# MemoryControl.net
KiCad netlist of a schematic drawn in Altium Designer
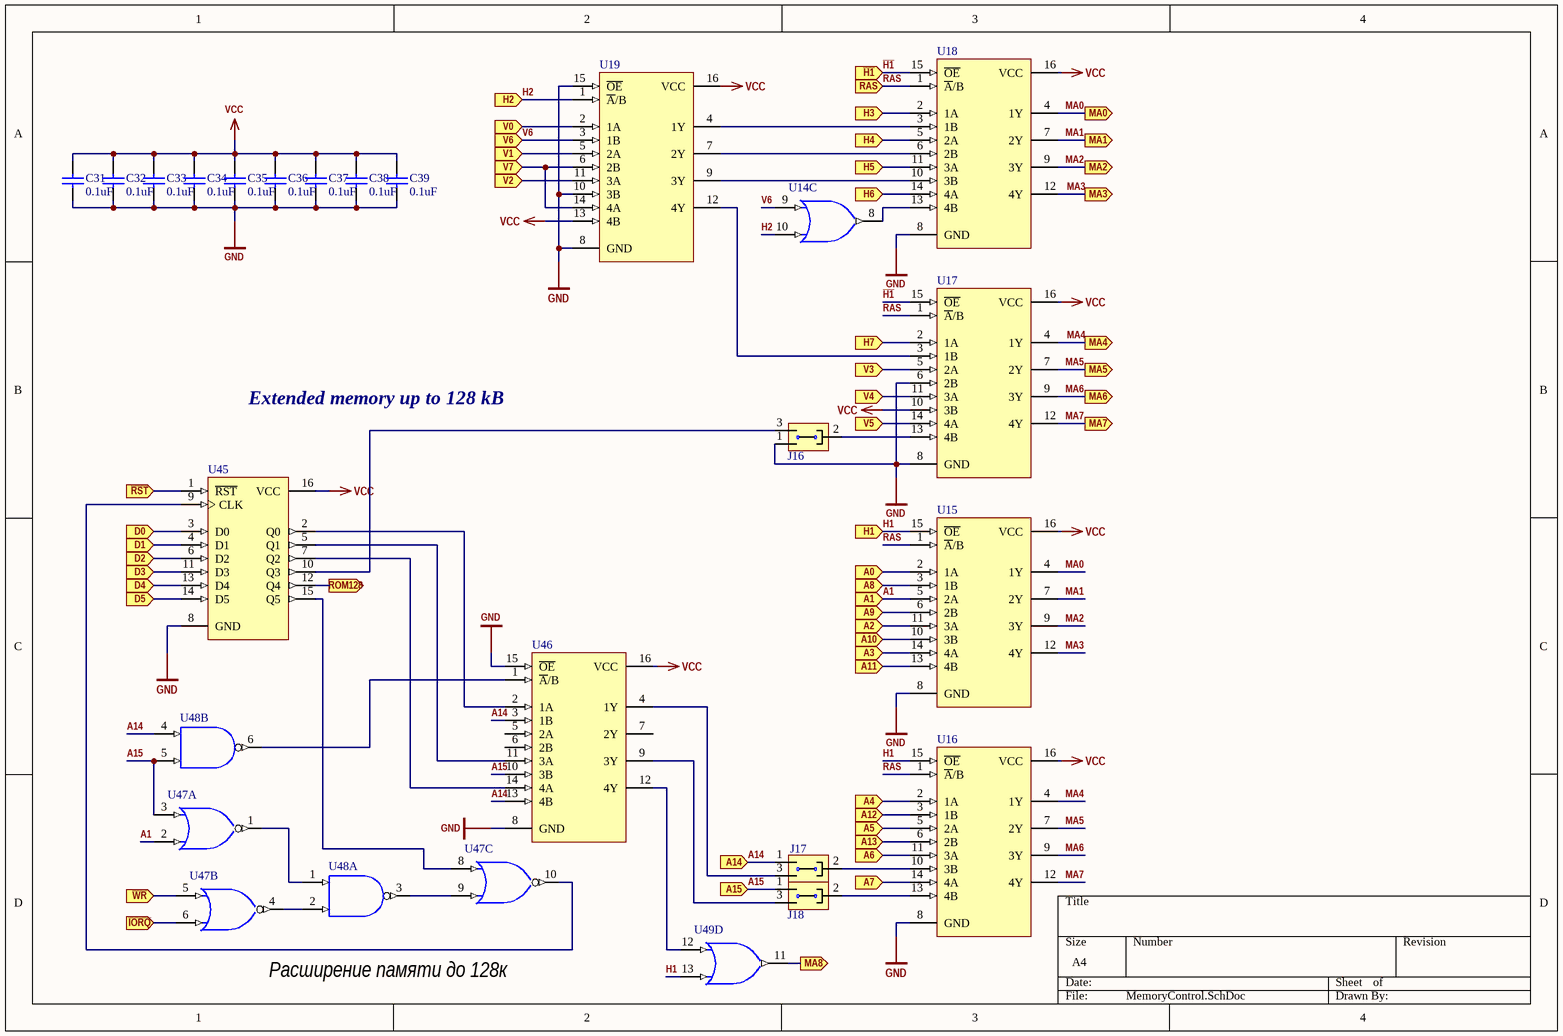
[diagram p0: MemoryControl.SchDoc]

(export (version "E")
  (design (tool "Eeschema 10.0.6"))
  (components
    (comp (ref "C31")
      (value "0.1uF")
      (footprint "RAD-0.3")
      (description "Capacitor")
      (fields (field (name "Comment") "Cap") (field (name "PUBLISHER") "Altium Limited"))
      (libsource (lib "Lenin") (part "Cap"))
    )
    (comp (ref "C32")
      (value "0.1uF")
      (footprint "RAD-0.3")
      (description "Capacitor")
      (fields (field (name "Comment") "Cap") (field (name "PUBLISHER") "Altium Limited"))
      (libsource (lib "Lenin") (part "Cap"))
    )
    (comp (ref "C33")
      (value "0.1uF")
      (footprint "RAD-0.3")
      (description "Capacitor")
      (fields (field (name "Comment") "Cap") (field (name "PUBLISHER") "Altium Limited"))
      (libsource (lib "Lenin") (part "Cap"))
    )
    (comp (ref "C34")
      (value "0.1uF")
      (footprint "RAD-0.3")
      (description "Capacitor")
      (fields (field (name "Comment") "Cap") (field (name "PUBLISHER") "Altium Limited"))
      (libsource (lib "Lenin") (part "Cap"))
    )
    (comp (ref "C35")
      (value "0.1uF")
      (footprint "RAD-0.3")
      (description "Capacitor")
      (fields (field (name "Comment") "Cap") (field (name "PUBLISHER") "Altium Limited"))
      (libsource (lib "Lenin") (part "Cap"))
    )
    (comp (ref "C36")
      (value "0.1uF")
      (footprint "RAD-0.3")
      (description "Capacitor")
      (fields (field (name "Comment") "Cap") (field (name "PUBLISHER") "Altium Limited"))
      (libsource (lib "Lenin") (part "Cap"))
    )
    (comp (ref "C37")
      (value "0.1uF")
      (footprint "RAD-0.3")
      (description "Capacitor")
      (fields (field (name "Comment") "Cap") (field (name "PUBLISHER") "Altium Limited"))
      (libsource (lib "Lenin") (part "Cap"))
    )
    (comp (ref "C38")
      (value "0.1uF")
      (footprint "RAD-0.3")
      (description "Capacitor")
      (fields (field (name "Comment") "Cap") (field (name "PUBLISHER") "Altium Limited"))
      (libsource (lib "Lenin") (part "Cap"))
    )
    (comp (ref "C39")
      (value "0.1uF")
      (footprint "RAD-0.3")
      (description "Capacitor")
      (fields (field (name "Comment") "Cap") (field (name "PUBLISHER") "Altium Limited"))
      (libsource (lib "Lenin") (part "Cap"))
    )
    (comp (ref "J16")
      (value "Jump3")
      (footprint "Miscellaneous Connectors:MHDR1X3")
      (libsource (lib "Lenin") (part "Jump3"))
    )
    (comp (ref "J17")
      (value "Jump3")
      (footprint "Miscellaneous Connectors:MHDR1X3")
      (libsource (lib "") (part "Jump3_1"))
    )
    (comp (ref "J18")
      (value "Jump3")
      (footprint "Miscellaneous Connectors:MHDR1X3")
      (libsource (lib "") (part "Jump3_1"))
    )
    (comp (ref "U14")
      (value "~")
      (footprint "N014")
      (description "Quadruple 2-Input Positive-OR Gate")
      (fields (field (name "PUBLISHER") "Altium Limited"))
      (libsource (lib "TI Logic Gate 2") (part "SN74HC32N"))
    )
    (comp (ref "U15")
      (value "~")
      (footprint "N016")
      (description "Quadruple 2-Line to 1-Line Data Selector/Multiplexer with 3-State Outputs")
      (fields (field (name "PUBLISHER") "Altium Limited"))
      (libsource (lib "TI Logic Multiplexer") (part "SN74HC257N"))
    )
    (comp (ref "U16")
      (value "~")
      (footprint "N016")
      (description "Quadruple 2-Line to 1-Line Data Selector/Multiplexer with 3-State Outputs")
      (fields (field (name "PUBLISHER") "Altium Limited"))
      (libsource (lib "TI Logic Multiplexer") (part "SN74HC257N"))
    )
    (comp (ref "U17")
      (value "~")
      (footprint "N016")
      (description "Quadruple 2-Line to 1-Line Data Selector/Multiplexer with 3-State Outputs")
      (fields (field (name "PUBLISHER") "Altium Limited"))
      (libsource (lib "TI Logic Multiplexer") (part "SN74HC257N"))
    )
    (comp (ref "U18")
      (value "~")
      (footprint "N016")
      (description "Quadruple 2-Line to 1-Line Data Selector/Multiplexer with 3-State Outputs")
      (fields (field (name "PUBLISHER") "Altium Limited"))
      (libsource (lib "TI Logic Multiplexer") (part "SN74HC257N"))
    )
    (comp (ref "U19")
      (value "~")
      (footprint "N016")
      (description "Quadruple 2-Line to 1-Line Data Selector/Multiplexer with 3-State Outputs")
      (fields (field (name "PUBLISHER") "Altium Limited"))
      (libsource (lib "TI Logic Multiplexer") (part "SN74HC257N"))
    )
    (comp (ref "U45")
      (value "SN74HC174N")
      (footprint "N016")
      (description "Hex D-Type Flip-Flop with Clear")
      (fields (field (name "PUBLISHER") "Altium Limited"))
      (libsource (lib "TI Logic Flip-Flop") (part "SN74HC174N"))
    )
    (comp (ref "U46")
      (value "SN74HC257N")
      (footprint "N016")
      (description "Quadruple 2-Line to 1-Line Data Selector/Multiplexer with 3-State Outputs")
      (fields (field (name "PUBLISHER") "Altium Limited"))
      (libsource (lib "TI Logic Multiplexer") (part "SN74HC257N"))
    )
    (comp (ref "U47")
      (value "SN74HC02N")
      (footprint "N014")
      (description "Quadruple 2-Input Positive-NOR Gate")
      (fields (field (name "PUBLISHER") "Altium Limited"))
      (libsource (lib "TI Logic Gate 2") (part "SN74HC02N"))
    )
    (comp (ref "U48")
      (value "SN74HC00N")
      (footprint "N014")
      (description "Quadruple 2-Input Positive-NAND Gate")
      (fields (field (name "PUBLISHER") "Altium Limited"))
      (libsource (lib "TI Logic Gate 2") (part "SN74HC00N"))
    )
    (comp (ref "U49")
      (value "SN74HC32N")
      (footprint "N014")
      (description "Quadruple 2-Input Positive-OR Gate")
      (fields (field (name "PUBLISHER") "Altium Limited"))
      (libsource (lib "TI Logic Gate 2") (part "SN74HC32N"))
    )
  )
  (nets
    (net (code "1") (name "/A0") (class "Default")
      (node (ref "U15") (pin "2") (pinfunction "1A_2") (pintype "input"))
    )
    (net (code "2") (name "/A1") (class "Default")
      (node (ref "U15") (pin "5") (pinfunction "2A_5") (pintype "input"))
      (node (ref "U47") (pin "2") (pinfunction "A_2") (pintype "input"))
    )
    (net (code "3") (name "/A2") (class "Default")
      (node (ref "U15") (pin "11") (pinfunction "3A_11") (pintype "input"))
    )
    (net (code "4") (name "/A3") (class "Default")
      (node (ref "U15") (pin "14") (pinfunction "4A_14") (pintype "input"))
    )
    (net (code "5") (name "/A4") (class "Default")
      (node (ref "U16") (pin "2") (pinfunction "1A_2") (pintype "input"))
    )
    (net (code "6") (name "/A5") (class "Default")
      (node (ref "U16") (pin "5") (pinfunction "2A_5") (pintype "input"))
    )
    (net (code "7") (name "/A6") (class "Default")
      (node (ref "U16") (pin "11") (pinfunction "3A_11") (pintype "input"))
    )
    (net (code "8") (name "/A7") (class "Default")
      (node (ref "U16") (pin "14") (pinfunction "4A_14") (pintype "input"))
    )
    (net (code "9") (name "/A8") (class "Default")
      (node (ref "U15") (pin "3") (pinfunction "1B_3") (pintype "input"))
    )
    (net (code "10") (name "/A9") (class "Default")
      (node (ref "U15") (pin "6") (pinfunction "2B_6") (pintype "input"))
    )
    (net (code "11") (name "/A10") (class "Default")
      (node (ref "U15") (pin "10") (pinfunction "3B_10") (pintype "input"))
    )
    (net (code "12") (name "/A11") (class "Default")
      (node (ref "U15") (pin "13") (pinfunction "4B_13") (pintype "input"))
    )
    (net (code "13") (name "/A12") (class "Default")
      (node (ref "U16") (pin "3") (pinfunction "1B_3") (pintype "input"))
    )
    (net (code "14") (name "/A13") (class "Default")
      (node (ref "U16") (pin "6") (pinfunction "2B_6") (pintype "input"))
    )
    (net (code "15") (name "/A14") (class "Default")
      (node (ref "J17") (pin "1") (pintype "passive"))
      (node (ref "U46") (pin "13") (pinfunction "4B_13") (pintype "input"))
      (node (ref "U46") (pin "3") (pinfunction "1B_3") (pintype "input"))
      (node (ref "U48") (pin "4") (pinfunction "A_4") (pintype "input"))
    )
    (net (code "16") (name "/A15") (class "Default")
      (node (ref "J18") (pin "1") (pintype "passive"))
      (node (ref "U46") (pin "10") (pinfunction "3B_10") (pintype "input"))
      (node (ref "U47") (pin "3") (pinfunction "B_3") (pintype "input"))
      (node (ref "U48") (pin "5") (pinfunction "B_5") (pintype "input"))
    )
    (net (code "17") (name "/D0") (class "Default")
      (node (ref "U45") (pin "3") (pinfunction "D0_3") (pintype "input"))
    )
    (net (code "18") (name "/D1") (class "Default")
      (node (ref "U45") (pin "4") (pinfunction "D1_4") (pintype "input"))
    )
    (net (code "19") (name "/D2") (class "Default")
      (node (ref "U45") (pin "6") (pinfunction "D2_6") (pintype "input"))
    )
    (net (code "20") (name "/D3") (class "Default")
      (node (ref "U45") (pin "11") (pinfunction "D3_11") (pintype "input"))
    )
    (net (code "21") (name "/D4") (class "Default")
      (node (ref "U45") (pin "13") (pinfunction "D4_13") (pintype "input"))
    )
    (net (code "22") (name "/D5") (class "Default")
      (node (ref "U45") (pin "14") (pinfunction "D5_14") (pintype "input"))
    )
    (net (code "23") (name "/H1") (class "Default")
      (node (ref "U15") (pin "15") (pinfunction "~{OE}_15") (pintype "input"))
      (node (ref "U16") (pin "15") (pinfunction "~{OE}_15") (pintype "input"))
      (node (ref "U49") (pin "13") (pinfunction "B_13") (pintype "input"))
    )
    (net (code "24") (name "/H2") (class "Default")
      (node (ref "U14") (pin "10") (pinfunction "B_10") (pintype "input"))
      (node (ref "U19") (pin "1") (pinfunction "~{A}/B_1") (pintype "input"))
    )
    (net (code "25") (name "/H3") (class "Default")
      (node (ref "U18") (pin "2") (pinfunction "1A_2") (pintype "input"))
    )
    (net (code "26") (name "/H4") (class "Default")
      (node (ref "U18") (pin "5") (pinfunction "2A_5") (pintype "input"))
    )
    (net (code "27") (name "/H5") (class "Default")
      (node (ref "U18") (pin "11") (pinfunction "3A_11") (pintype "input"))
    )
    (net (code "28") (name "/H6") (class "Default")
      (node (ref "U18") (pin "14") (pinfunction "4A_14") (pintype "input"))
    )
    (net (code "29") (name "/H7") (class "Default")
      (node (ref "U17") (pin "2") (pinfunction "1A_2") (pintype "input"))
    )
    (net (code "30") (name "/MA0") (class "Default")
      (node (ref "U15") (pin "4") (pinfunction "1Y_4") (pintype "tri_state"))
      (node (ref "U18") (pin "4") (pinfunction "1Y_4") (pintype "tri_state"))
    )
    (net (code "31") (name "/MA1") (class "Default")
      (node (ref "U15") (pin "7") (pinfunction "2Y_7") (pintype "tri_state"))
      (node (ref "U18") (pin "7") (pinfunction "2Y_7") (pintype "tri_state"))
    )
    (net (code "32") (name "/MA2") (class "Default")
      (node (ref "U15") (pin "9") (pinfunction "3Y_9") (pintype "tri_state"))
      (node (ref "U18") (pin "9") (pinfunction "3Y_9") (pintype "tri_state"))
    )
    (net (code "33") (name "/MA3") (class "Default")
      (node (ref "U15") (pin "12") (pinfunction "4Y_12") (pintype "tri_state"))
      (node (ref "U18") (pin "12") (pinfunction "4Y_12") (pintype "tri_state"))
    )
    (net (code "34") (name "/MA4") (class "Default")
      (node (ref "U16") (pin "4") (pinfunction "1Y_4") (pintype "tri_state"))
      (node (ref "U17") (pin "4") (pinfunction "1Y_4") (pintype "tri_state"))
    )
    (net (code "35") (name "/MA5") (class "Default")
      (node (ref "U16") (pin "7") (pinfunction "2Y_7") (pintype "tri_state"))
      (node (ref "U17") (pin "7") (pinfunction "2Y_7") (pintype "tri_state"))
    )
    (net (code "36") (name "/MA6") (class "Default")
      (node (ref "U16") (pin "9") (pinfunction "3Y_9") (pintype "tri_state"))
      (node (ref "U17") (pin "9") (pinfunction "3Y_9") (pintype "tri_state"))
    )
    (net (code "37") (name "/MA7") (class "Default")
      (node (ref "U16") (pin "12") (pinfunction "4Y_12") (pintype "tri_state"))
      (node (ref "U17") (pin "12") (pinfunction "4Y_12") (pintype "tri_state"))
    )
    (net (code "38") (name "/MA8") (class "Default")
      (node (ref "U49") (pin "11") (pinfunction "Y_11") (pintype "output"))
    )
    (net (code "39") (name "/RAS") (class "Default")
      (node (ref "U15") (pin "1") (pinfunction "~{A}/B_1") (pintype "input"))
      (node (ref "U16") (pin "1") (pinfunction "~{A}/B_1") (pintype "input"))
      (node (ref "U17") (pin "1") (pinfunction "~{A}/B_1") (pintype "input"))
      (node (ref "U18") (pin "1") (pinfunction "~{A}/B_1") (pintype "input"))
    )
    (net (code "40") (name "/ROM128") (class "Default")
      (node (ref "U45") (pin "12") (pinfunction "Q4_12") (pintype "output"))
    )
    (net (code "41") (name "/V0") (class "Default")
      (node (ref "U19") (pin "2") (pinfunction "1A_2") (pintype "input"))
    )
    (net (code "42") (name "/V1") (class "Default")
      (node (ref "U19") (pin "5") (pinfunction "2A_5") (pintype "input"))
    )
    (net (code "43") (name "/V2") (class "Default")
      (node (ref "U19") (pin "11") (pinfunction "3A_11") (pintype "input"))
    )
    (net (code "44") (name "/V3") (class "Default")
      (node (ref "U17") (pin "5") (pinfunction "2A_5") (pintype "input"))
    )
    (net (code "45") (name "/V4") (class "Default")
      (node (ref "U17") (pin "11") (pinfunction "3A_11") (pintype "input"))
    )
    (net (code "46") (name "/V5") (class "Default")
      (node (ref "U17") (pin "14") (pinfunction "4A_14") (pintype "input"))
    )
    (net (code "47") (name "/V6") (class "Default")
      (node (ref "U14") (pin "9") (pinfunction "A_9") (pintype "input"))
      (node (ref "U19") (pin "3") (pinfunction "1B_3") (pintype "input"))
    )
    (net (code "48") (name "/V7") (class "Default")
      (node (ref "U19") (pin "14") (pinfunction "4A_14") (pintype "input"))
      (node (ref "U19") (pin "6") (pinfunction "2B_6") (pintype "input"))
    )
    (net (code "49") (name "/~{H1}") (class "Default")
      (node (ref "U17") (pin "15") (pinfunction "~{OE}_15") (pintype "input"))
      (node (ref "U18") (pin "15") (pinfunction "~{OE}_15") (pintype "input"))
    )
    (net (code "50") (name "/~{IORQ}") (class "Default")
      (node (ref "U47") (pin "6") (pinfunction "B_6") (pintype "input"))
    )
    (net (code "51") (name "/~{RST}") (class "Default")
      (node (ref "U45") (pin "1") (pinfunction "~{RST}_1") (pintype "input"))
    )
    (net (code "52") (name "/~{WR}") (class "Default")
      (node (ref "U47") (pin "5") (pinfunction "A_5") (pintype "input"))
    )
    (net (code "53") (name "GND") (class "Default")
      (node (ref "C31") (pin "1") (pinfunction "1_1") (pintype "passive"))
      (node (ref "C32") (pin "1") (pinfunction "1_1") (pintype "passive"))
      (node (ref "C33") (pin "1") (pinfunction "1_1") (pintype "passive"))
      (node (ref "C34") (pin "1") (pinfunction "1_1") (pintype "passive"))
      (node (ref "C35") (pin "1") (pinfunction "1_1") (pintype "passive"))
      (node (ref "C36") (pin "1") (pinfunction "1_1") (pintype "passive"))
      (node (ref "C37") (pin "1") (pinfunction "1_1") (pintype "passive"))
      (node (ref "C38") (pin "1") (pinfunction "1_1") (pintype "passive"))
      (node (ref "C39") (pin "1") (pinfunction "1_1") (pintype "passive"))
      (node (ref "J16") (pin "1") (pintype "passive"))
      (node (ref "U14") (pin "7") (pinfunction "GND_7") (pintype "power_in"))
      (node (ref "U15") (pin "8") (pinfunction "GND_8") (pintype "power_in"))
      (node (ref "U16") (pin "8") (pinfunction "GND_8") (pintype "power_in"))
      (node (ref "U17") (pin "6") (pinfunction "2B_6") (pintype "input"))
      (node (ref "U17") (pin "8") (pinfunction "GND_8") (pintype "power_in"))
      (node (ref "U18") (pin "8") (pinfunction "GND_8") (pintype "power_in"))
      (node (ref "U19") (pin "10") (pinfunction "3B_10") (pintype "input"))
      (node (ref "U19") (pin "15") (pinfunction "~{OE}_15") (pintype "input"))
      (node (ref "U19") (pin "8") (pinfunction "GND_8") (pintype "power_in"))
      (node (ref "U45") (pin "8") (pinfunction "GND_8") (pintype "power_in"))
      (node (ref "U46") (pin "15") (pinfunction "~{OE}_15") (pintype "input"))
      (node (ref "U46") (pin "8") (pinfunction "GND_8") (pintype "power_in"))
      (node (ref "U47") (pin "7") (pinfunction "GND_7") (pintype "power_in"))
      (node (ref "U48") (pin "7") (pinfunction "GND_7") (pintype "power_in"))
      (node (ref "U49") (pin "7") (pinfunction "GND_7") (pintype "power_in"))
    )
    (net (code "54") (name "Net-(U14C-Y)") (class "Default")
      (node (ref "U14") (pin "8") (pinfunction "Y_8") (pintype "output"))
      (node (ref "U18") (pin "13") (pinfunction "4B_13") (pintype "input"))
    )
    (net (code "55") (name "Net-(U16-3B)") (class "Default")
      (node (ref "J17") (pin "2") (pintype "passive"))
      (node (ref "U16") (pin "10") (pinfunction "3B_10") (pintype "input"))
    )
    (net (code "56") (name "Net-(U16-4B)") (class "Default")
      (node (ref "J18") (pin "2") (pintype "passive"))
      (node (ref "U16") (pin "13") (pinfunction "4B_13") (pintype "input"))
    )
    (net (code "57") (name "Net-(U17-1B)") (class "Default")
      (node (ref "U17") (pin "3") (pinfunction "1B_3") (pintype "input"))
      (node (ref "U19") (pin "12") (pinfunction "4Y_12") (pintype "tri_state"))
    )
    (net (code "58") (name "Net-(U17-4B)") (class "Default")
      (node (ref "J16") (pin "2") (pintype "passive"))
      (node (ref "U17") (pin "13") (pinfunction "4B_13") (pintype "input"))
    )
    (net (code "59") (name "Net-(U18-1B)") (class "Default")
      (node (ref "U18") (pin "3") (pinfunction "1B_3") (pintype "input"))
      (node (ref "U19") (pin "4") (pinfunction "1Y_4") (pintype "tri_state"))
    )
    (net (code "60") (name "Net-(U18-2B)") (class "Default")
      (node (ref "U18") (pin "6") (pinfunction "2B_6") (pintype "input"))
      (node (ref "U19") (pin "7") (pinfunction "2Y_7") (pintype "tri_state"))
    )
    (net (code "61") (name "Net-(U18-3B)") (class "Default")
      (node (ref "U18") (pin "10") (pinfunction "3B_10") (pintype "input"))
      (node (ref "U19") (pin "9") (pinfunction "3Y_9") (pintype "tri_state"))
    )
    (net (code "62") (name "Net-(U45-CLK)") (class "Default")
      (node (ref "U45") (pin "9") (pinfunction "CLK_9") (pintype "input"))
      (node (ref "U47") (pin "10") (pinfunction "Y_10") (pintype "output"))
    )
    (net (code "63") (name "Net-(U45-Q0)") (class "Default")
      (node (ref "U45") (pin "2") (pinfunction "Q0_2") (pintype "output"))
      (node (ref "U46") (pin "2") (pinfunction "1A_2") (pintype "input"))
    )
    (net (code "64") (name "Net-(U45-Q1)") (class "Default")
      (node (ref "U45") (pin "5") (pinfunction "Q1_5") (pintype "output"))
      (node (ref "U46") (pin "11") (pinfunction "3A_11") (pintype "input"))
    )
    (net (code "65") (name "Net-(U45-Q2)") (class "Default")
      (node (ref "U45") (pin "7") (pinfunction "Q2_7") (pintype "output"))
      (node (ref "U46") (pin "14") (pinfunction "4A_14") (pintype "input"))
    )
    (net (code "66") (name "Net-(U45-Q3)") (class "Default")
      (node (ref "J16") (pin "3") (pintype "passive"))
      (node (ref "U45") (pin "10") (pinfunction "Q3_10") (pintype "output"))
    )
    (net (code "67") (name "Net-(U45-Q5)") (class "Default")
      (node (ref "U45") (pin "15") (pinfunction "Q5_15") (pintype "output"))
      (node (ref "U47") (pin "8") (pinfunction "A_8") (pintype "input"))
    )
    (net (code "68") (name "Net-(U46-1Y)") (class "Default")
      (node (ref "J17") (pin "3") (pintype "passive"))
      (node (ref "U46") (pin "4") (pinfunction "1Y_4") (pintype "tri_state"))
    )
    (net (code "69") (name "Net-(U46-3Y)") (class "Default")
      (node (ref "J18") (pin "3") (pintype "passive"))
      (node (ref "U46") (pin "9") (pinfunction "3Y_9") (pintype "tri_state"))
    )
    (net (code "70") (name "Net-(U46-4Y)") (class "Default")
      (node (ref "U46") (pin "12") (pinfunction "4Y_12") (pintype "tri_state"))
      (node (ref "U49") (pin "12") (pinfunction "A_12") (pintype "input"))
    )
    (net (code "71") (name "Net-(U46-~{A}{slash}B)") (class "Default")
      (node (ref "U46") (pin "1") (pinfunction "~{A}/B_1") (pintype "input"))
      (node (ref "U48") (pin "6") (pinfunction "Y_6") (pintype "output"))
    )
    (net (code "72") (name "Net-(U47A-Y)") (class "Default")
      (node (ref "U47") (pin "1") (pinfunction "Y_1") (pintype "output"))
      (node (ref "U48") (pin "1") (pinfunction "A_1") (pintype "input"))
    )
    (net (code "73") (name "Net-(U47B-Y)") (class "Default")
      (node (ref "U47") (pin "4") (pinfunction "Y_4") (pintype "output"))
      (node (ref "U48") (pin "2") (pinfunction "B_2") (pintype "input"))
    )
    (net (code "74") (name "Net-(U47C-B)") (class "Default")
      (node (ref "U47") (pin "9") (pinfunction "B_9") (pintype "input"))
      (node (ref "U48") (pin "3") (pinfunction "Y_3") (pintype "output"))
    )
    (net (code "75") (name "VCC") (class "Default")
      (node (ref "C31") (pin "2") (pinfunction "2_2") (pintype "passive"))
      (node (ref "C32") (pin "2") (pinfunction "2_2") (pintype "passive"))
      (node (ref "C33") (pin "2") (pinfunction "2_2") (pintype "passive"))
      (node (ref "C34") (pin "2") (pinfunction "2_2") (pintype "passive"))
      (node (ref "C35") (pin "2") (pinfunction "2_2") (pintype "passive"))
      (node (ref "C36") (pin "2") (pinfunction "2_2") (pintype "passive"))
      (node (ref "C37") (pin "2") (pinfunction "2_2") (pintype "passive"))
      (node (ref "C38") (pin "2") (pinfunction "2_2") (pintype "passive"))
      (node (ref "C39") (pin "2") (pinfunction "2_2") (pintype "passive"))
      (node (ref "U14") (pin "14") (pinfunction "VCC_14") (pintype "power_in"))
      (node (ref "U15") (pin "16") (pinfunction "VCC_16") (pintype "power_in"))
      (node (ref "U16") (pin "16") (pinfunction "VCC_16") (pintype "power_in"))
      (node (ref "U17") (pin "10") (pinfunction "3B_10") (pintype "input"))
      (node (ref "U17") (pin "16") (pinfunction "VCC_16") (pintype "power_in"))
      (node (ref "U18") (pin "16") (pinfunction "VCC_16") (pintype "power_in"))
      (node (ref "U19") (pin "13") (pinfunction "4B_13") (pintype "input"))
      (node (ref "U19") (pin "16") (pinfunction "VCC_16") (pintype "power_in"))
      (node (ref "U45") (pin "16") (pinfunction "VCC_16") (pintype "power_in"))
      (node (ref "U46") (pin "16") (pinfunction "VCC_16") (pintype "power_in"))
      (node (ref "U47") (pin "14") (pinfunction "VCC_14") (pintype "power_in"))
      (node (ref "U48") (pin "14") (pinfunction "VCC_14") (pintype "power_in"))
      (node (ref "U49") (pin "14") (pinfunction "VCC_14") (pintype "power_in"))
    )
    (net (code "76") (name "unconnected-(U46-2A-Pad5)") (class "Default")
      (node (ref "U46") (pin "5") (pinfunction "2A_5") (pintype "input"))
    )
    (net (code "77") (name "unconnected-(U46-2B-Pad6)") (class "Default")
      (node (ref "U46") (pin "6") (pinfunction "2B_6") (pintype "input"))
    )
    (net (code "78") (name "unconnected-(U46-2Y-Pad7)") (class "Default")
      (node (ref "U46") (pin "7") (pinfunction "2Y_7") (pintype "tri_state"))
    )
  )
)
